# lm386_nogain_v2.net
KiCad netlist of a schematic drawn in EAGLE
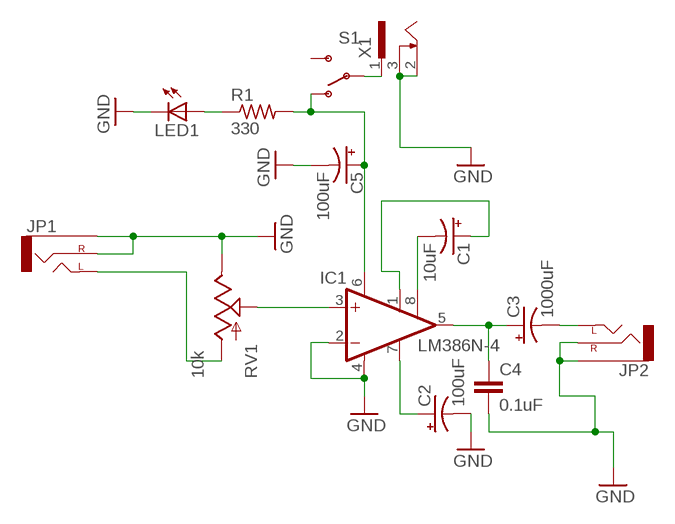
[diagram p0: schematic, sheet 1]

(export (version "E")
  (design (tool "Eeschema 10.0.6"))
  (components
    (comp (ref "C1")
      (value "10uF")
      (footprint "eagle-import:CPOL-RADIAL-10UF-25V")
      (libsource (lib "eagle-import") (part "CAP_POLPTH2"))
    )
    (comp (ref "C2")
      (value "100uF")
      (footprint "eagle-import:CPOL-RADIAL-10UF-25V")
      (libsource (lib "eagle-import") (part "CAP_POLPTH2"))
    )
    (comp (ref "C3")
      (value "1000uF")
      (footprint "eagle-import:CPOL-RADIAL-10UF-25V")
      (libsource (lib "eagle-import") (part "CAP_POLPTH2"))
    )
    (comp (ref "C4")
      (value "0.1uF")
      (footprint "eagle-import:CAP-PTH-SMALL2")
      (libsource (lib "eagle-import") (part "CAPPTH2"))
    )
    (comp (ref "C5")
      (value "100uF")
      (footprint "eagle-import:CPOL-RADIAL-100UF-25V")
      (libsource (lib "eagle-import") (part "100UF-25V-20%(PTH)"))
    )
    (comp (ref "IC1")
      (value "LM386N-4")
      (footprint "eagle-import:DIL08")
      (libsource (lib "eagle-import") (part "LM386?-N4"))
    )
    (comp (ref "JP1")
      (value "AUDIO-JACKPTH")
      (footprint "eagle-import:AUDIO-JACK")
      (libsource (lib "eagle-import") (part "AUDIO-JACKPTH"))
    )
    (comp (ref "JP2")
      (value "AUDIO-JACKPTH")
      (footprint "eagle-import:AUDIO-JACK")
      (libsource (lib "eagle-import") (part "AUDIO-JACKPTH"))
    )
    (comp (ref "LED1")
      (value "LED5MM")
      (footprint "eagle-import:LED5MM")
      (libsource (lib "eagle-import") (part "LED5MM"))
    )
    (comp (ref "R1")
      (value "330")
      (footprint "eagle-import:0204V")
      (libsource (lib "eagle-import") (part "R-US_0204/2V"))
    )
    (comp (ref "RV1")
      (value "10k")
      (footprint "eagle-import:ALPS_POT")
      (libsource (lib "eagle-import") (part "POT"))
    )
    (comp (ref "S1")
      (value "SWITCH-SPDTPTH_LOCK")
      (footprint "eagle-import:SWITCH-SPDT_LOCK.007S")
      (libsource (lib "eagle-import") (part "SWITCH-SPDTPTH_LOCK"))
    )
    (comp (ref "X1")
      (value "SCD-014A")
      (footprint "eagle-import:SCD-014-A")
      (libsource (lib "eagle-import") (part "SCD-014A"))
    )
  )
  (nets
    (net (code "1") (name "GND") (class "Default")
      (node (ref "C2") (pin "2") (pinfunction "-_2") (pintype "passive"))
      (node (ref "C4") (pin "2") (pinfunction "2_2") (pintype "passive"))
      (node (ref "C5") (pin "2") (pinfunction "-_2") (pintype "passive"))
      (node (ref "IC1") (pin "2") (pinfunction "-IN_2") (pintype "input"))
      (node (ref "IC1") (pin "4") (pinfunction "GND_4") (pintype "power_in"))
      (node (ref "JP1") (pin "RING") (pinfunction "RIGHT_RING") (pintype "bidirectional"))
      (node (ref "JP1") (pin "SLEEVE") (pinfunction "SLEEVE_SLEEVE") (pintype "bidirectional"))
      (node (ref "JP2") (pin "RING") (pinfunction "RIGHT_RING") (pintype "bidirectional"))
      (node (ref "JP2") (pin "SLEEVE") (pinfunction "SLEEVE_SLEEVE") (pintype "bidirectional"))
      (node (ref "LED1") (pin "K") (pinfunction "C_K") (pintype "passive"))
      (node (ref "RV1") (pin "P$1") (pinfunction "E_P$1") (pintype "passive"))
      (node (ref "X1") (pin "2") (pinfunction "2_2") (pintype "passive"))
      (node (ref "X1") (pin "3") (pinfunction "3_3") (pintype "passive"))
    )
    (net (code "2") (name "Net-(C1-+)") (class "Default")
      (node (ref "C1") (pin "1") (pinfunction "+_1") (pintype "passive"))
      (node (ref "IC1") (pin "1") (pinfunction "GAIN_1") (pintype "passive"))
    )
    (net (code "3") (name "Net-(C1--)") (class "Default")
      (node (ref "C1") (pin "2") (pinfunction "-_2") (pintype "passive"))
      (node (ref "IC1") (pin "8") (pinfunction "GAIN_8") (pintype "passive"))
    )
    (net (code "4") (name "Net-(C2-+)") (class "Default")
      (node (ref "C2") (pin "1") (pinfunction "+_1") (pintype "passive"))
      (node (ref "IC1") (pin "7") (pinfunction "BYPASS_7") (pintype "passive"))
    )
    (net (code "5") (name "Net-(C3-+)") (class "Default")
      (node (ref "C3") (pin "1") (pinfunction "+_1") (pintype "passive"))
      (node (ref "C4") (pin "1") (pinfunction "1_1") (pintype "passive"))
      (node (ref "IC1") (pin "5") (pinfunction "OUT_5") (pintype "output"))
    )
    (net (code "6") (name "Net-(C3--)") (class "Default")
      (node (ref "C3") (pin "2") (pinfunction "-_2") (pintype "passive"))
      (node (ref "JP2") (pin "TIP") (pinfunction "LEFT_TIP") (pintype "bidirectional"))
    )
    (net (code "7") (name "Net-(C5-+)") (class "Default")
      (node (ref "C5") (pin "1") (pinfunction "+_1") (pintype "passive"))
      (node (ref "IC1") (pin "6") (pinfunction "VS_6") (pintype "power_in"))
      (node (ref "R1") (pin "2") (pinfunction "2_2") (pintype "passive"))
      (node (ref "S1") (pin "1") (pinfunction "O_1") (pintype "passive"))
    )
    (net (code "8") (name "Net-(IC1-+IN)") (class "Default")
      (node (ref "IC1") (pin "3") (pinfunction "+IN_3") (pintype "input"))
      (node (ref "RV1") (pin "P$2") (pinfunction "S_P$2") (pintype "passive"))
    )
    (net (code "9") (name "Net-(JP1-LEFT)") (class "Default")
      (node (ref "JP1") (pin "TIP") (pinfunction "LEFT_TIP") (pintype "bidirectional"))
      (node (ref "RV1") (pin "P$3") (pinfunction "A_P$3") (pintype "passive"))
    )
    (net (code "10") (name "Net-(LED1-PadA)") (class "Default")
      (node (ref "LED1") (pin "A") (pinfunction "A_A") (pintype "passive"))
      (node (ref "R1") (pin "1") (pinfunction "1_1") (pintype "passive"))
    )
    (net (code "11") (name "Net-(S1-P)") (class "Default")
      (node (ref "S1") (pin "2") (pinfunction "P_2") (pintype "passive"))
      (node (ref "X1") (pin "1") (pinfunction "1_1") (pintype "passive"))
    )
    (net (code "12") (name "unconnected-(S1-S-Pad3)") (class "Default")
      (node (ref "S1") (pin "3") (pinfunction "S_3") (pintype "passive"))
    )
  )
)
